# macropad.net
KiCad netlist of a schematic drawn in EasyEDA Pro
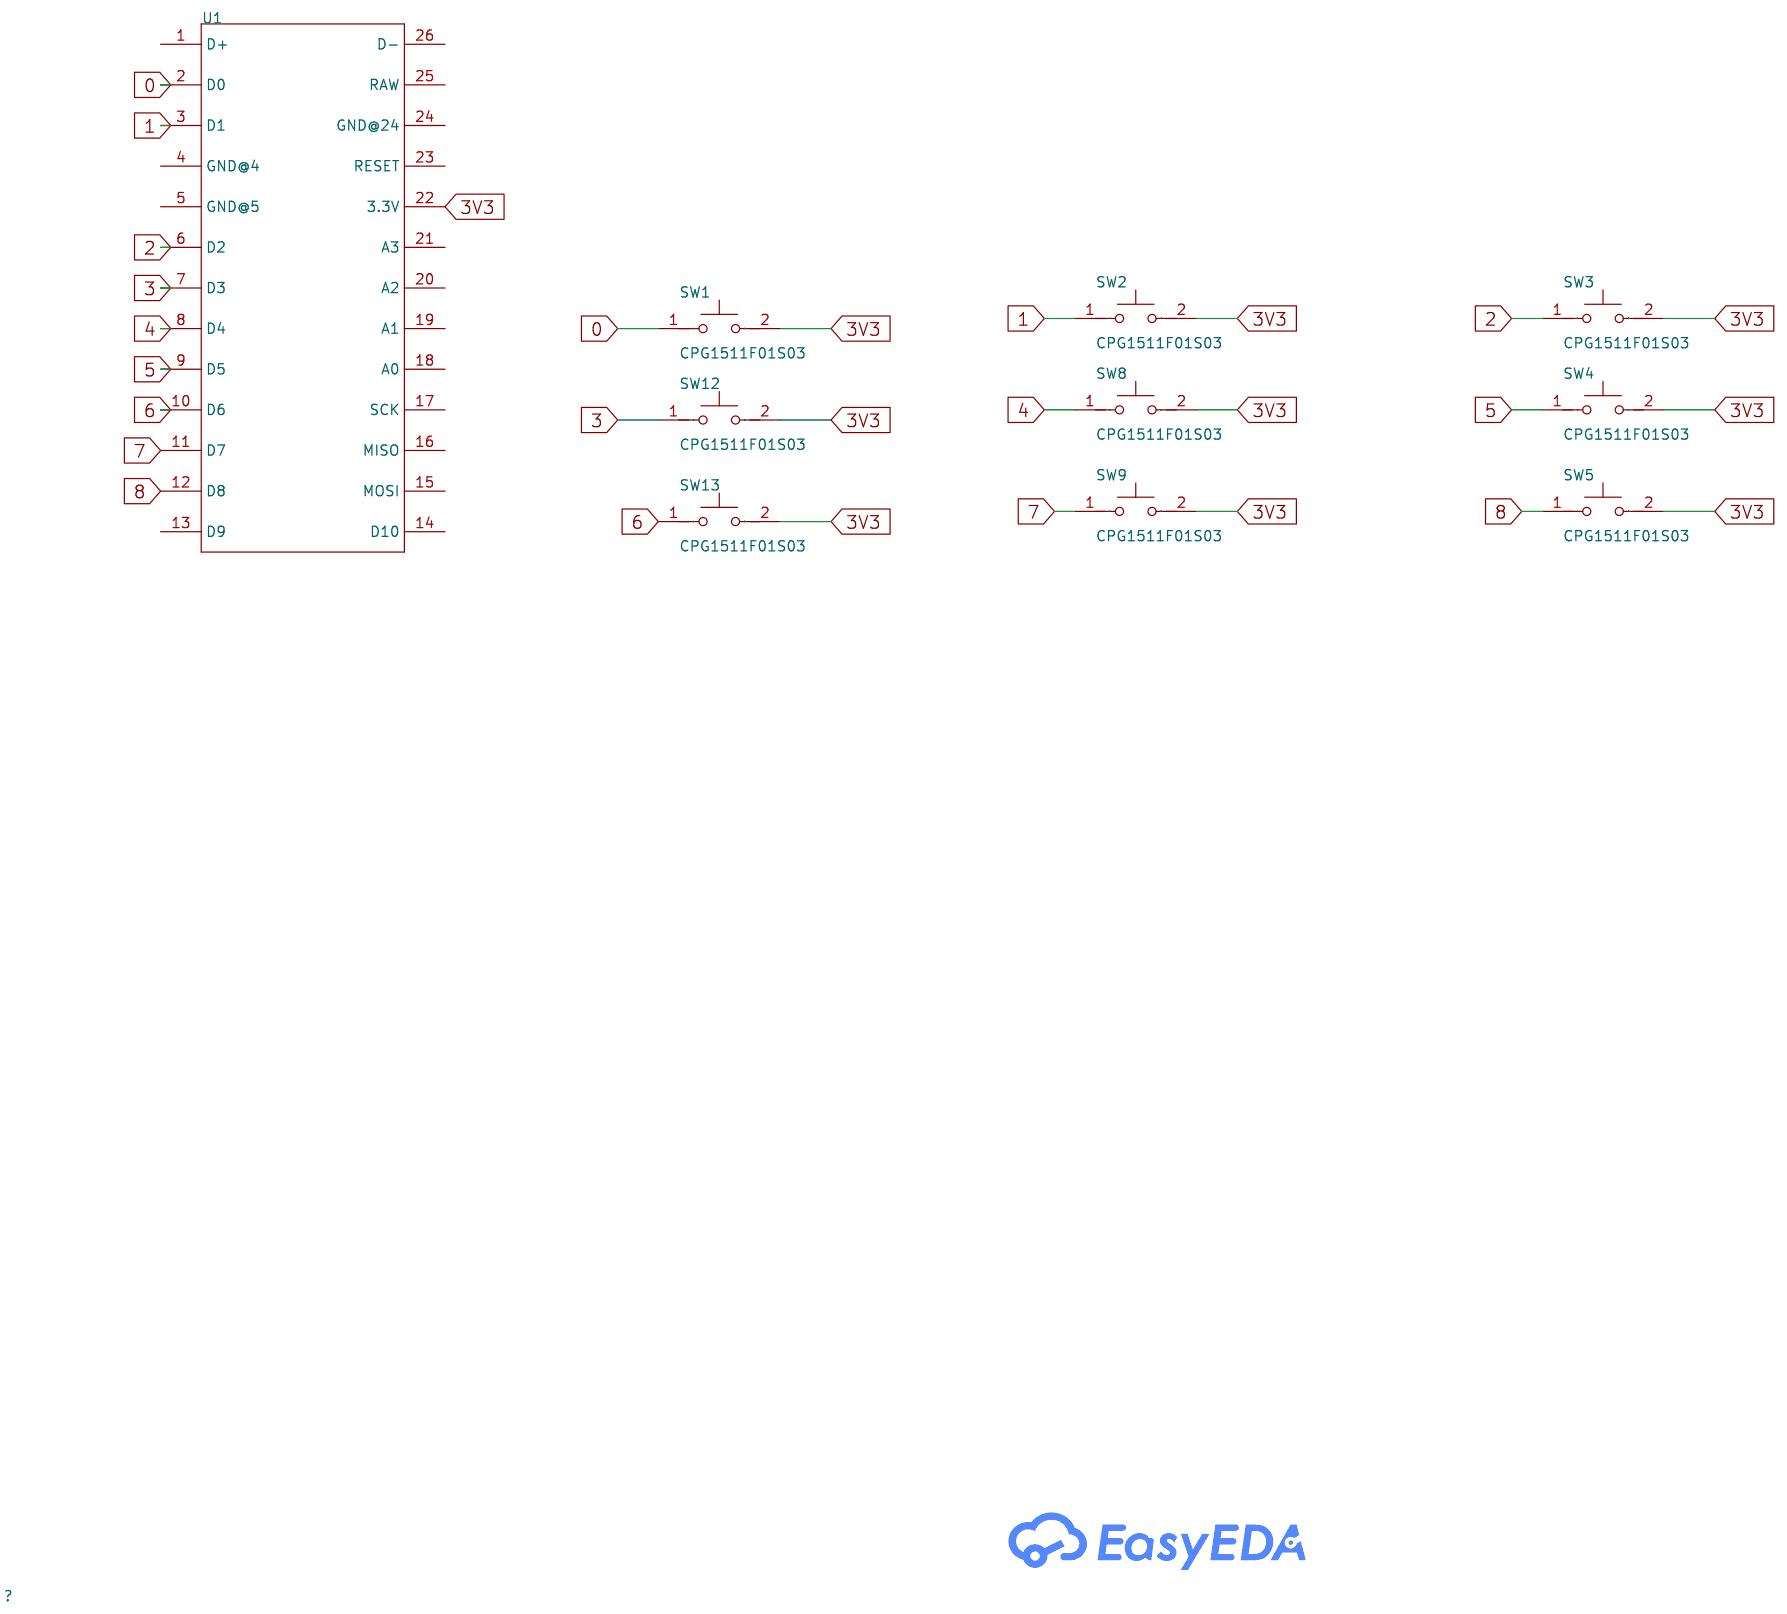
[diagram p0: schematic sheet]

(export (version "E")
  (design (tool "Eeschema 10.0.6"))
  (components
    (comp (ref "SW1")
      (value "CPG1511F01S03")
      (footprint "easyedapro:KEY-TH_CPG1511F01S0X")
      (fields (field (name "Manufacturer") "Kailh(凯华)"))
      (libsource (lib "easyedapro") (part "CPG1511F01S03"))
    )
    (comp (ref "SW2")
      (value "CPG1511F01S03")
      (footprint "easyedapro:KEY-TH_CPG1511F01S0X")
      (fields (field (name "Manufacturer") "Kailh(凯华)"))
      (libsource (lib "easyedapro") (part "CPG1511F01S03"))
    )
    (comp (ref "SW3")
      (value "CPG1511F01S03")
      (footprint "easyedapro:KEY-TH_CPG1511F01S0X")
      (fields (field (name "Manufacturer") "Kailh(凯华)"))
      (libsource (lib "easyedapro") (part "CPG1511F01S03"))
    )
    (comp (ref "SW4")
      (value "CPG1511F01S03")
      (footprint "easyedapro:KEY-TH_CPG1511F01S0X")
      (fields (field (name "Manufacturer") "Kailh(凯华)"))
      (libsource (lib "easyedapro") (part "CPG1511F01S03"))
    )
    (comp (ref "SW5")
      (value "CPG1511F01S03")
      (footprint "easyedapro:KEY-TH_CPG1511F01S0X")
      (fields (field (name "Manufacturer") "Kailh(凯华)"))
      (libsource (lib "easyedapro") (part "CPG1511F01S03"))
    )
    (comp (ref "SW8")
      (value "CPG1511F01S03")
      (footprint "easyedapro:KEY-TH_CPG1511F01S0X")
      (fields (field (name "Manufacturer") "Kailh(凯华)"))
      (libsource (lib "easyedapro") (part "CPG1511F01S03"))
    )
    (comp (ref "SW9")
      (value "CPG1511F01S03")
      (footprint "easyedapro:KEY-TH_CPG1511F01S0X")
      (fields (field (name "Manufacturer") "Kailh(凯华)"))
      (libsource (lib "easyedapro") (part "CPG1511F01S03"))
    )
    (comp (ref "SW12")
      (value "CPG1511F01S03")
      (footprint "easyedapro:KEY-TH_CPG1511F01S0X")
      (fields (field (name "Manufacturer") "Kailh(凯华)"))
      (libsource (lib "easyedapro") (part "CPG1511F01S03"))
    )
    (comp (ref "SW13")
      (value "CPG1511F01S03")
      (footprint "easyedapro:KEY-TH_CPG1511F01S0X")
      (fields (field (name "Manufacturer") "Kailh(凯华)"))
      (libsource (lib "easyedapro") (part "CPG1511F01S03"))
    )
    (comp (ref "U1") (value "~") (libsource (lib "easyedapro") (part "KB2040")))
  )
  (nets
    (net (code "1") (name "0") (class "Default")
      (node (ref "SW1") (pin "1") (pinfunction "1_1") (pintype "unspecified"))
      (node (ref "U1") (pin "2") (pinfunction "D0_2") (pintype "bidirectional"))
    )
    (net (code "2") (name "1") (class "Default")
      (node (ref "SW2") (pin "1") (pinfunction "1_1") (pintype "unspecified"))
      (node (ref "U1") (pin "3") (pinfunction "D1_3") (pintype "bidirectional"))
    )
    (net (code "3") (name "2") (class "Default")
      (node (ref "SW3") (pin "1") (pinfunction "1_1") (pintype "unspecified"))
      (node (ref "U1") (pin "6") (pinfunction "D2_6") (pintype "bidirectional"))
    )
    (net (code "4") (name "3") (class "Default")
      (node (ref "SW12") (pin "1") (pinfunction "1_1") (pintype "unspecified"))
      (node (ref "U1") (pin "7") (pinfunction "D3_7") (pintype "bidirectional"))
    )
    (net (code "5") (name "3V3") (class "Default")
      (node (ref "SW1") (pin "2") (pinfunction "2_2") (pintype "unspecified"))
      (node (ref "SW12") (pin "2") (pinfunction "2_2") (pintype "unspecified"))
      (node (ref "SW13") (pin "2") (pinfunction "2_2") (pintype "unspecified"))
      (node (ref "SW2") (pin "2") (pinfunction "2_2") (pintype "unspecified"))
      (node (ref "SW3") (pin "2") (pinfunction "2_2") (pintype "unspecified"))
      (node (ref "SW4") (pin "2") (pinfunction "2_2") (pintype "unspecified"))
      (node (ref "SW5") (pin "2") (pinfunction "2_2") (pintype "unspecified"))
      (node (ref "SW8") (pin "2") (pinfunction "2_2") (pintype "unspecified"))
      (node (ref "SW9") (pin "2") (pinfunction "2_2") (pintype "unspecified"))
      (node (ref "U1") (pin "22") (pinfunction "3.3V_22") (pintype "bidirectional"))
    )
    (net (code "6") (name "4") (class "Default")
      (node (ref "SW8") (pin "1") (pinfunction "1_1") (pintype "unspecified"))
      (node (ref "U1") (pin "8") (pinfunction "D4_8") (pintype "bidirectional"))
    )
    (net (code "7") (name "5") (class "Default")
      (node (ref "SW4") (pin "1") (pinfunction "1_1") (pintype "unspecified"))
      (node (ref "U1") (pin "9") (pinfunction "D5_9") (pintype "bidirectional"))
    )
    (net (code "8") (name "6") (class "Default")
      (node (ref "SW13") (pin "1") (pinfunction "1_1") (pintype "unspecified"))
      (node (ref "U1") (pin "10") (pinfunction "D6_10") (pintype "bidirectional"))
    )
    (net (code "9") (name "7") (class "Default")
      (node (ref "SW9") (pin "1") (pinfunction "1_1") (pintype "unspecified"))
      (node (ref "U1") (pin "11") (pinfunction "D7_11") (pintype "bidirectional"))
    )
    (net (code "10") (name "8") (class "Default")
      (node (ref "SW5") (pin "1") (pinfunction "1_1") (pintype "unspecified"))
      (node (ref "U1") (pin "12") (pinfunction "D8_12") (pintype "bidirectional"))
    )
    (net (code "11") (name "unconnected-(U1-A0-Pad18)") (class "Default")
      (node (ref "U1") (pin "18") (pinfunction "A0_18") (pintype "bidirectional"))
    )
    (net (code "12") (name "unconnected-(U1-A1-Pad19)") (class "Default")
      (node (ref "U1") (pin "19") (pinfunction "A1_19") (pintype "bidirectional"))
    )
    (net (code "13") (name "unconnected-(U1-A2-Pad20)") (class "Default")
      (node (ref "U1") (pin "20") (pinfunction "A2_20") (pintype "bidirectional"))
    )
    (net (code "14") (name "unconnected-(U1-A3-Pad21)") (class "Default")
      (node (ref "U1") (pin "21") (pinfunction "A3_21") (pintype "bidirectional"))
    )
    (net (code "15") (name "unconnected-(U1-D+-Pad1)") (class "Default")
      (node (ref "U1") (pin "1") (pinfunction "D+_1") (pintype "bidirectional"))
    )
    (net (code "16") (name "unconnected-(U1-D--Pad26)") (class "Default")
      (node (ref "U1") (pin "26") (pinfunction "D-_26") (pintype "bidirectional"))
    )
    (net (code "17") (name "unconnected-(U1-D9-Pad13)") (class "Default")
      (node (ref "U1") (pin "13") (pinfunction "D9_13") (pintype "bidirectional"))
    )
    (net (code "18") (name "unconnected-(U1-D10-Pad14)") (class "Default")
      (node (ref "U1") (pin "14") (pinfunction "D10_14") (pintype "bidirectional"))
    )
    (net (code "19") (name "unconnected-(U1-GND@4-Pad4)") (class "Default")
      (node (ref "U1") (pin "4") (pinfunction "GND@4_4") (pintype "bidirectional"))
    )
    (net (code "20") (name "unconnected-(U1-GND@5-Pad5)") (class "Default")
      (node (ref "U1") (pin "5") (pinfunction "GND@5_5") (pintype "bidirectional"))
    )
    (net (code "21") (name "unconnected-(U1-GND@24-Pad24)") (class "Default")
      (node (ref "U1") (pin "24") (pinfunction "GND@24_24") (pintype "bidirectional"))
    )
    (net (code "22") (name "unconnected-(U1-MISO-Pad16)") (class "Default")
      (node (ref "U1") (pin "16") (pinfunction "MISO_16") (pintype "bidirectional"))
    )
    (net (code "23") (name "unconnected-(U1-MOSI-Pad15)") (class "Default")
      (node (ref "U1") (pin "15") (pinfunction "MOSI_15") (pintype "bidirectional"))
    )
    (net (code "24") (name "unconnected-(U1-RAW-Pad25)") (class "Default")
      (node (ref "U1") (pin "25") (pinfunction "RAW_25") (pintype "bidirectional"))
    )
    (net (code "25") (name "unconnected-(U1-RESET-Pad23)") (class "Default")
      (node (ref "U1") (pin "23") (pinfunction "RESET_23") (pintype "bidirectional"))
    )
    (net (code "26") (name "unconnected-(U1-SCK-Pad17)") (class "Default")
      (node (ref "U1") (pin "17") (pinfunction "SCK_17") (pintype "bidirectional"))
    )
  )
)
